# P1.net
KiCad netlist of a schematic drawn in EasyEDA Pro
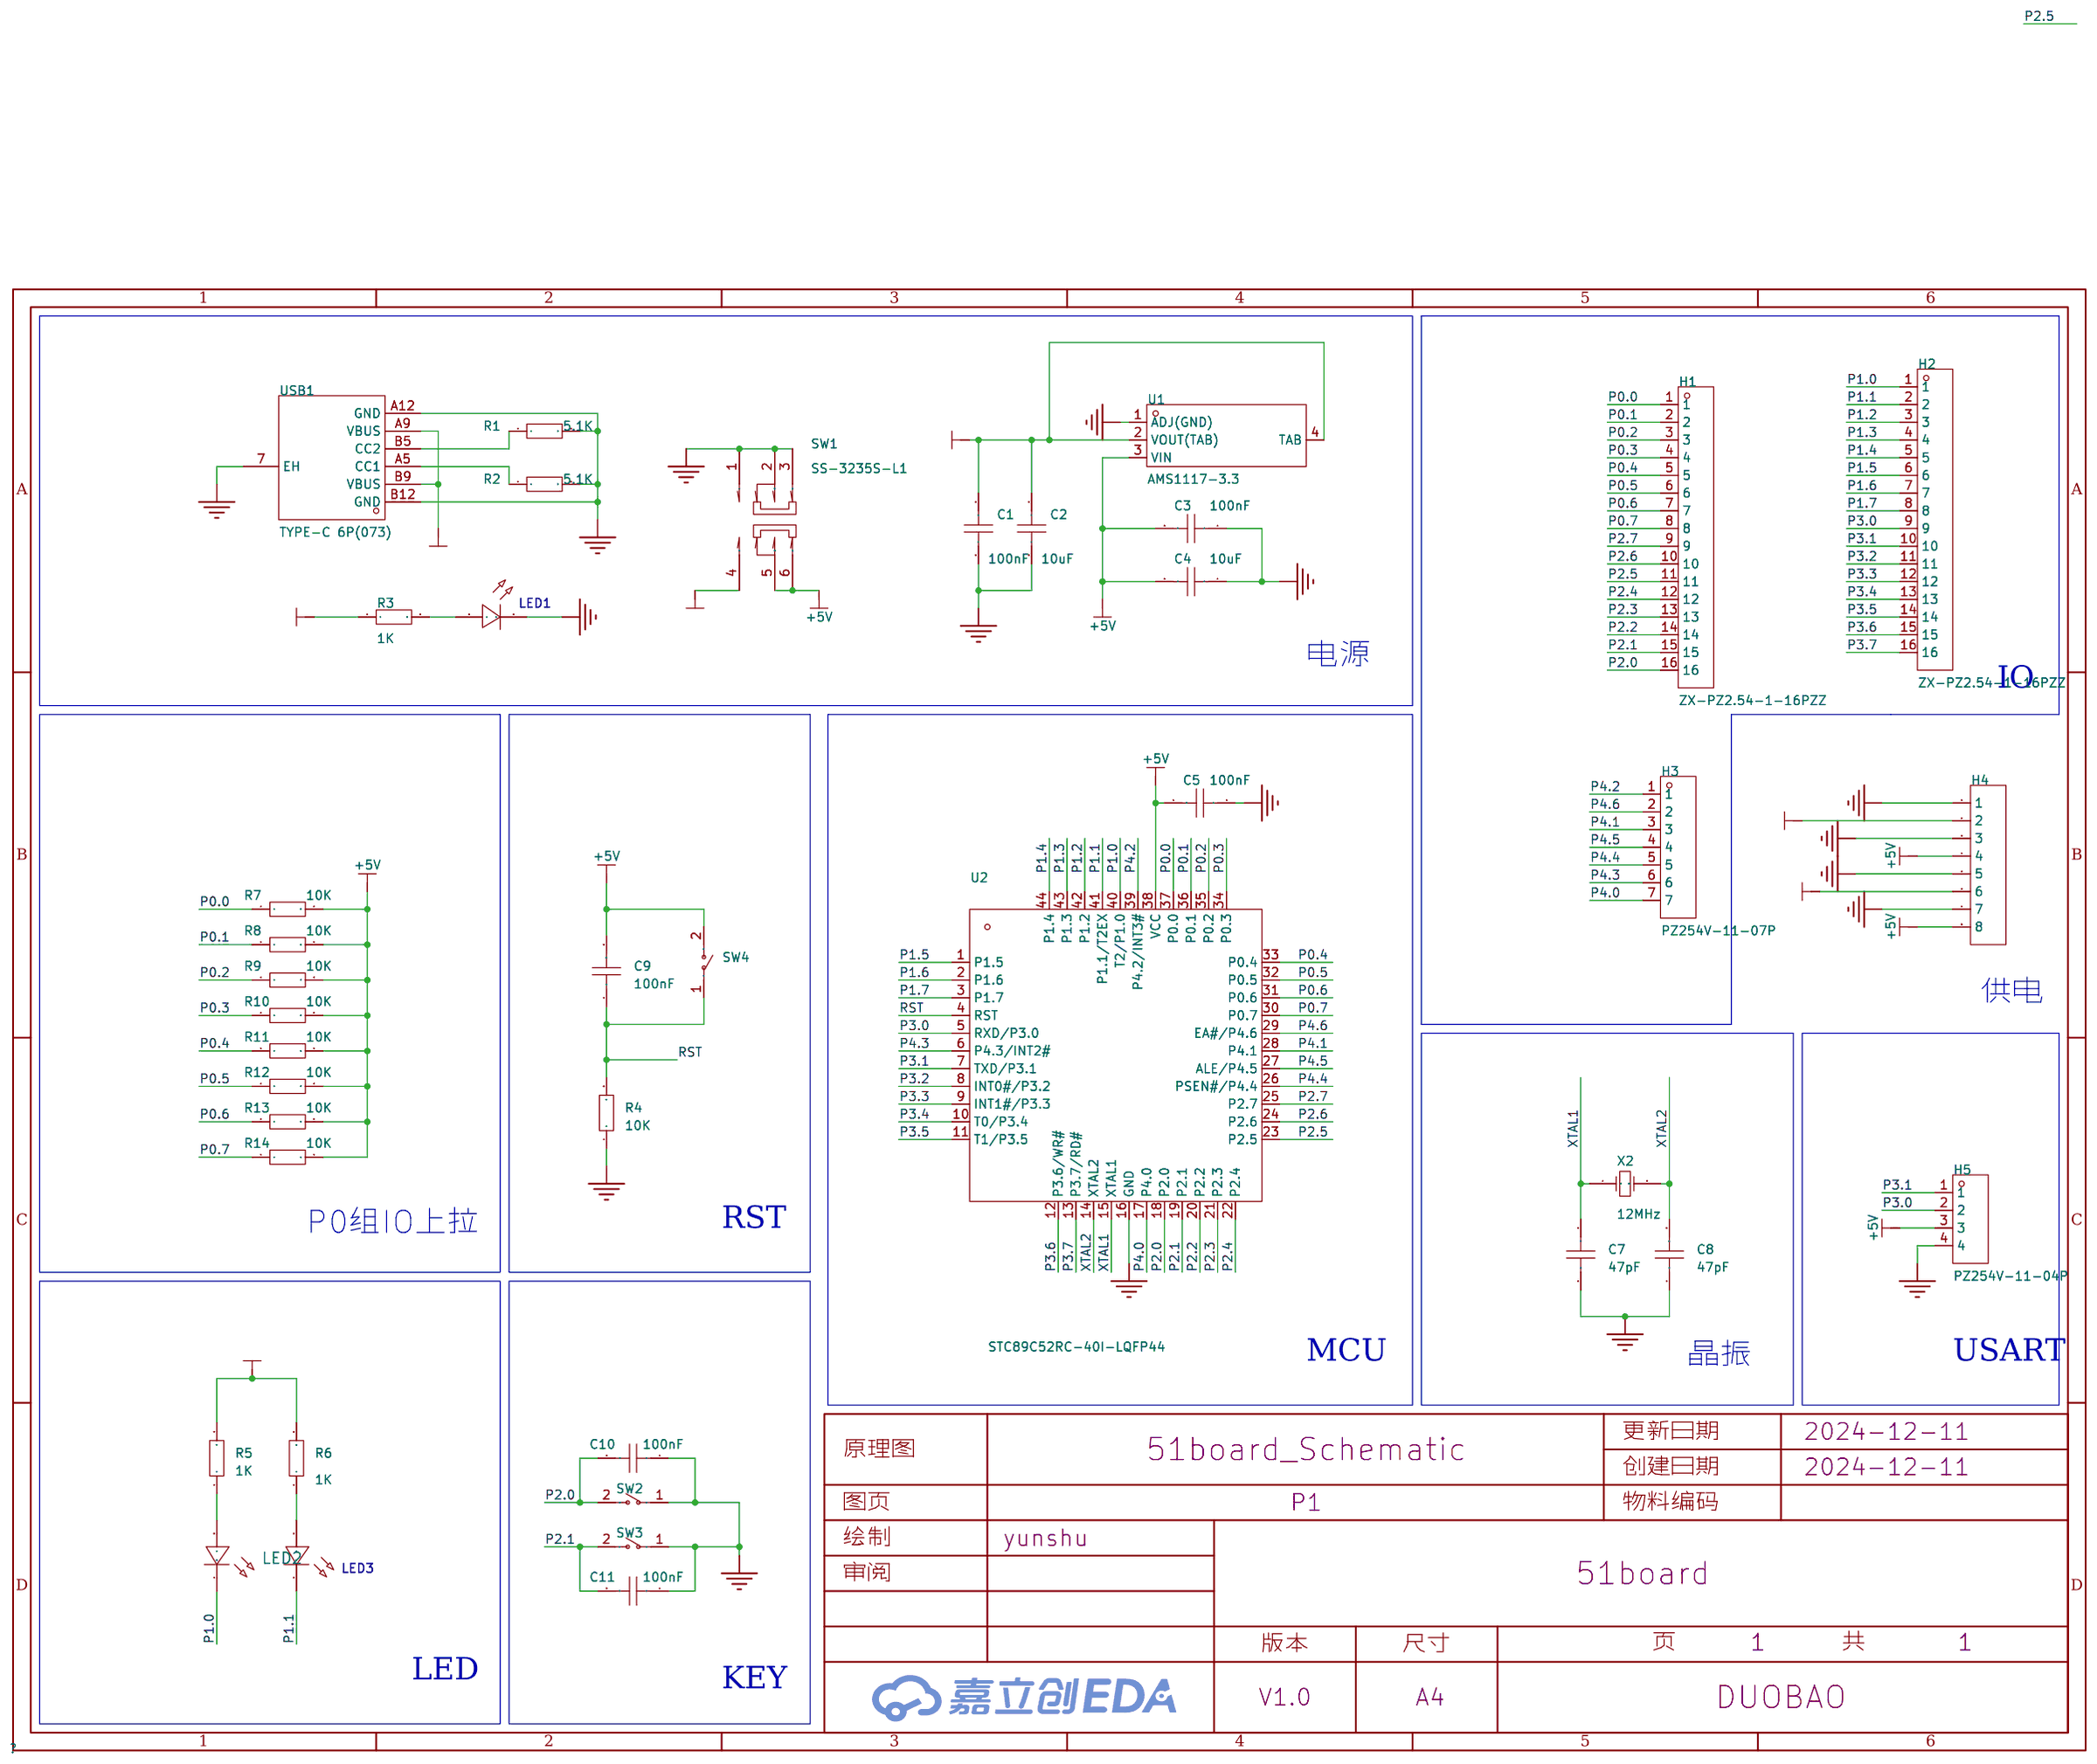
[diagram p0: schematic sheet]

(export (version "E")
  (design (tool "Eeschema 10.0.6"))
  (components
    (comp (ref "C1")
      (value "100nF")
      (footprint "easyedapro:C0805")
      (libsource (lib "easyedapro") (part "CapAcitance"))
    )
    (comp (ref "C2")
      (value "10uF")
      (footprint "easyedapro:C0805")
      (libsource (lib "easyedapro") (part "CapAcitance"))
    )
    (comp (ref "C3")
      (value "100nF")
      (footprint "easyedapro:C0805")
      (libsource (lib "easyedapro") (part "CapAcitance"))
    )
    (comp (ref "C4")
      (value "10uF")
      (footprint "easyedapro:C0805")
      (libsource (lib "easyedapro") (part "CapAcitance"))
    )
    (comp (ref "C5")
      (value "100nF")
      (footprint "easyedapro:C0805")
      (libsource (lib "easyedapro") (part "CapAcitance"))
    )
    (comp (ref "C7")
      (value "47pF")
      (footprint "easyedapro:C0805")
      (libsource (lib "easyedapro") (part "CapAcitance"))
    )
    (comp (ref "C8")
      (value "47pF")
      (footprint "easyedapro:C0805")
      (libsource (lib "easyedapro") (part "CapAcitance"))
    )
    (comp (ref "C9")
      (value "100nF")
      (footprint "easyedapro:C0805")
      (libsource (lib "easyedapro") (part "CapAcitance"))
    )
    (comp (ref "C10")
      (value "100nF")
      (footprint "easyedapro:C0805")
      (libsource (lib "easyedapro") (part "CapAcitance"))
    )
    (comp (ref "C11")
      (value "100nF")
      (footprint "easyedapro:C0805")
      (libsource (lib "easyedapro") (part "CapAcitance"))
    )
    (comp (ref "H1")
      (value "ZX-PZ2.54-1-16PZZ")
      (fields (field (name "Manufacturer") "Megastar(兆星)"))
      (libsource (lib "easyedapro") (part "HDR_2.54-1x16P"))
    )
    (comp (ref "H2")
      (value "ZX-PZ2.54-1-16PZZ")
      (fields (field (name "Manufacturer") "Megastar(兆星)"))
      (libsource (lib "easyedapro") (part "HDR_2.54-1x16P"))
    )
    (comp (ref "H3")
      (value "PZ254V-11-07P")
      (footprint "easyedapro:HDR-TH_7P-P2.54-V-M")
      (fields (field (name "Manufacturer") "XFCN(兴飞)"))
      (libsource (lib "easyedapro") (part "PZ254V-11-07P"))
    )
    (comp (ref "H4")
      (value "~")
      (footprint "easyedapro:HDR-TH_8P-P2.54-V-F-1")
      (libsource (lib "easyedapro") (part "Header-Female-2.54_1x8"))
    )
    (comp (ref "H5")
      (value "PZ254V-11-04P")
      (fields (field (name "Manufacturer") "XFCN(兴飞)"))
      (libsource (lib "easyedapro") (part "PZ254V-11-04P"))
    )
    (comp (ref "LED1")
      (value "~")
      (footprint "easyedapro:LED_0805")
      (libsource (lib "easyedapro") (part "LED_G"))
    )
    (comp (ref "LED2")
      (value "~")
      (footprint "easyedapro:LED_0805")
      (libsource (lib "easyedapro") (part "LED_R"))
    )
    (comp (ref "LED3")
      (value "~")
      (footprint "easyedapro:LED_0805")
      (libsource (lib "easyedapro") (part "LED_B"))
    )
    (comp (ref "R1") (value "5.1K") (footprint "easyedapro:R0805") (libsource (lib "easyedapro") (part "电阻")))
    (comp (ref "R2") (value "5.1K") (footprint "easyedapro:R0805") (libsource (lib "easyedapro") (part "电阻")))
    (comp (ref "R3") (value "1K") (footprint "easyedapro:R0805") (libsource (lib "easyedapro") (part "电阻")))
    (comp (ref "R4") (value "10K") (footprint "easyedapro:R0805") (libsource (lib "easyedapro") (part "电阻")))
    (comp (ref "R5") (value "1K") (footprint "easyedapro:R0805") (libsource (lib "easyedapro") (part "电阻")))
    (comp (ref "R6") (value "1K") (footprint "easyedapro:R0805") (libsource (lib "easyedapro") (part "电阻")))
    (comp (ref "R7") (value "10K") (footprint "easyedapro:R0805") (libsource (lib "easyedapro") (part "电阻")))
    (comp (ref "R8") (value "10K") (footprint "easyedapro:R0805") (libsource (lib "easyedapro") (part "电阻")))
    (comp (ref "R9") (value "10K") (footprint "easyedapro:R0805") (libsource (lib "easyedapro") (part "电阻")))
    (comp (ref "R10") (value "10K") (footprint "easyedapro:R0805") (libsource (lib "easyedapro") (part "电阻")))
    (comp (ref "R11") (value "10K") (footprint "easyedapro:R0805") (libsource (lib "easyedapro") (part "电阻")))
    (comp (ref "R12") (value "10K") (footprint "easyedapro:R0805") (libsource (lib "easyedapro") (part "电阻")))
    (comp (ref "R13") (value "10K") (footprint "easyedapro:R0805") (libsource (lib "easyedapro") (part "电阻")))
    (comp (ref "R14") (value "10K") (footprint "easyedapro:R0805") (libsource (lib "easyedapro") (part "电阻")))
    (comp (ref "SW1")
      (value "SS-3235S-L1")
      (footprint "easyedapro:SW-SMD_SS-3235S-LX")
      (description "电路结构:双刀双掷;安装方式:卧贴;开关颜色:黑色;额定电流(DC):50mA;额定电压(DC):12V;额定电流(AC):50mA;额定电压(AC):12V;机械寿命:1万次;")
      (fields (field (name "Manufacturer") "XKB Connectivity(中国星坤)"))
      (libsource (lib "easyedapro") (part "SS-3235S-L1"))
    )
    (comp (ref "SW2")
      (value "轻触按键 3x6x2.5mm")
      (footprint "easyedapro:SW-SMD_L6.1-W3.7-LS8.0")
      (description "开关长度:6.05mm;开关宽度:3.65mm;开关高度:2.5mm;机械寿命:-;")
      (fields (field (name "Manufacturer") "BBJ"))
      (libsource (lib "easyedapro") (part "轻触按键 3X6X2.5MM"))
    )
    (comp (ref "SW3")
      (value "轻触按键 3x6x2.5mm")
      (footprint "easyedapro:SW-SMD_L6.1-W3.7-LS8.0")
      (description "开关长度:6.05mm;开关宽度:3.65mm;开关高度:2.5mm;机械寿命:-;")
      (fields (field (name "Manufacturer") "BBJ"))
      (libsource (lib "easyedapro") (part "轻触按键 3X6X2.5MM"))
    )
    (comp (ref "SW4")
      (value "轻触按键 3x6x2.5mm")
      (footprint "easyedapro:SW-SMD_L6.1-W3.7-LS8.0")
      (description "开关长度:6.05mm;开关宽度:3.65mm;开关高度:2.5mm;机械寿命:-;")
      (fields (field (name "Manufacturer") "BBJ"))
      (libsource (lib "easyedapro") (part "轻触按键 3X6X2.5MM"))
    )
    (comp (ref "U1")
      (value "AMS1117-3.3")
      (footprint "easyedapro:SOT-223-4_L6.5-W3.5-P2.30-LS7.0-BR")
      (description "输出类型:固定;最大输入电压:18V;输出电压:3.3V;输出电流:1A;电源纹波抑制比(PSRR):60dB@(120Hz);输出极性:正极;")
      (fields (field (name "Manufacturer") "UMW(友台半导体)"))
      (libsource (lib "easyedapro") (part "AMS1117-3.3_C347222"))
    )
    (comp (ref "U2")
      (value "STC89C52RC-40I-LQFP44")
      (footprint "easyedapro:LQFP-44_L10.0-W10.0-P0.80-LS12.0-BL")
      (description "CPU内核:51系列;程序存储容量:8KB;RAM总容量:512Byte;GPIO端口数量:39;工作电压范围:3.3V~5.5V;CPU最大主频:-;程序存储器类型:FLASH;")
      (fields (field (name "Manufacturer") "STC(宏晶)"))
      (libsource (lib "easyedapro") (part "STC89C52RC-40I_C8707"))
    )
    (comp (ref "USB1")
      (value "TYPE-C 6P(073)")
      (footprint "easyedapro:TYPE-C-SMD_TYPE-C-6P_5")
      (description "连接器类型:Type-C;标准:USB 3.1;公母:母;安装方式:卧贴;触点数量:6P;端口数量:1;额定电流 - 电源:3A;工作温度范围:-25°C~+85°C;")
      (fields (field (name "Manufacturer") "SHOU HAN(首韩)"))
      (libsource (lib "easyedapro") (part "TYPE-C 6P(073)"))
    )
    (comp (ref "X2")
      (value "12MHz")
      (footprint "easyedapro:OSC-TH_BD2.0-P0.50")
      (description "晶振类型:直插晶振;频率:12MHz;常温频差:±20ppm;外接负载电容:20pF;频率稳定度(全温):±30ppm;")
      (fields
        (field (name "Manufacturer Part") "TXD12M0002206LDBEO00S")
        (field (name "Manufacturer") "YJX(雅晶鑫)")
      )
      (libsource (lib "easyedapro") (part "TXD12M0002206LDBEO00S"))
    )
  )
  (nets
    (net (code "1") (name "+5V") (class "Default")
      (node (ref "C3") (pin "2") (pinfunction "2_2") (pintype "input"))
      (node (ref "C4") (pin "2") (pinfunction "2_2") (pintype "input"))
      (node (ref "C5") (pin "1") (pinfunction "1_1") (pintype "input"))
      (node (ref "C9") (pin "2") (pinfunction "2_2") (pintype "input"))
      (node (ref "H4") (pin "4") (pinfunction "4_4") (pintype "input"))
      (node (ref "H4") (pin "8") (pinfunction "8_8") (pintype "input"))
      (node (ref "H5") (pin "3") (pinfunction "3_3") (pintype "unspecified"))
      (node (ref "R10") (pin "2") (pinfunction "2_2") (pintype "input"))
      (node (ref "R11") (pin "2") (pinfunction "2_2") (pintype "input"))
      (node (ref "R12") (pin "2") (pinfunction "2_2") (pintype "input"))
      (node (ref "R13") (pin "2") (pinfunction "2_2") (pintype "input"))
      (node (ref "R14") (pin "2") (pinfunction "2_2") (pintype "input"))
      (node (ref "R7") (pin "2") (pinfunction "2_2") (pintype "input"))
      (node (ref "R8") (pin "2") (pinfunction "2_2") (pintype "input"))
      (node (ref "R9") (pin "2") (pinfunction "2_2") (pintype "input"))
      (node (ref "SW1") (pin "5") (pinfunction "5_5") (pintype "unspecified"))
      (node (ref "SW1") (pin "6") (pinfunction "6_6") (pintype "unspecified"))
      (node (ref "SW4") (pin "2") (pinfunction "2_2") (pintype "unspecified"))
      (node (ref "U1") (pin "3") (pinfunction "VIN_3") (pintype "unspecified"))
      (node (ref "U2") (pin "38") (pinfunction "VCC_38") (pintype "unspecified"))
    )
    (net (code "2") (name "/P0.0") (class "Default")
      (node (ref "H1") (pin "1") (pinfunction "1_1") (pintype "input"))
      (node (ref "R7") (pin "1") (pinfunction "1_1") (pintype "input"))
      (node (ref "U2") (pin "37") (pinfunction "P0.0_37") (pintype "unspecified"))
    )
    (net (code "3") (name "/P0.1") (class "Default")
      (node (ref "H1") (pin "2") (pinfunction "2_2") (pintype "input"))
      (node (ref "R8") (pin "1") (pinfunction "1_1") (pintype "input"))
      (node (ref "U2") (pin "36") (pinfunction "P0.1_36") (pintype "unspecified"))
    )
    (net (code "4") (name "/P0.2") (class "Default")
      (node (ref "H1") (pin "3") (pinfunction "3_3") (pintype "input"))
      (node (ref "R9") (pin "1") (pinfunction "1_1") (pintype "input"))
      (node (ref "U2") (pin "35") (pinfunction "P0.2_35") (pintype "unspecified"))
    )
    (net (code "5") (name "/P0.3") (class "Default")
      (node (ref "H1") (pin "4") (pinfunction "4_4") (pintype "input"))
      (node (ref "R10") (pin "1") (pinfunction "1_1") (pintype "input"))
      (node (ref "U2") (pin "34") (pinfunction "P0.3_34") (pintype "unspecified"))
    )
    (net (code "6") (name "/P0.4") (class "Default")
      (node (ref "H1") (pin "5") (pinfunction "5_5") (pintype "input"))
      (node (ref "R11") (pin "1") (pinfunction "1_1") (pintype "input"))
      (node (ref "U2") (pin "33") (pinfunction "P0.4_33") (pintype "unspecified"))
    )
    (net (code "7") (name "/P0.5") (class "Default")
      (node (ref "H1") (pin "6") (pinfunction "6_6") (pintype "input"))
      (node (ref "R12") (pin "1") (pinfunction "1_1") (pintype "input"))
      (node (ref "U2") (pin "32") (pinfunction "P0.5_32") (pintype "unspecified"))
    )
    (net (code "8") (name "/P0.6") (class "Default")
      (node (ref "H1") (pin "7") (pinfunction "7_7") (pintype "input"))
      (node (ref "R13") (pin "1") (pinfunction "1_1") (pintype "input"))
      (node (ref "U2") (pin "31") (pinfunction "P0.6_31") (pintype "unspecified"))
    )
    (net (code "9") (name "/P0.7") (class "Default")
      (node (ref "H1") (pin "8") (pinfunction "8_8") (pintype "input"))
      (node (ref "R14") (pin "1") (pinfunction "1_1") (pintype "input"))
      (node (ref "U2") (pin "30") (pinfunction "P0.7_30") (pintype "unspecified"))
    )
    (net (code "10") (name "/P1.0") (class "Default")
      (node (ref "H2") (pin "1") (pinfunction "1_1") (pintype "input"))
      (node (ref "LED2") (pin "1") (pinfunction "C_1") (pintype "input"))
      (node (ref "U2") (pin "40") (pinfunction "T2/P1.0_40") (pintype "unspecified"))
    )
    (net (code "11") (name "/P1.1") (class "Default")
      (node (ref "H2") (pin "2") (pinfunction "2_2") (pintype "input"))
      (node (ref "LED3") (pin "1") (pinfunction "C_1") (pintype "input"))
      (node (ref "U2") (pin "41") (pinfunction "P1.1/T2EX_41") (pintype "unspecified"))
    )
    (net (code "12") (name "/P1.2") (class "Default")
      (node (ref "H2") (pin "3") (pinfunction "3_3") (pintype "input"))
      (node (ref "U2") (pin "42") (pinfunction "P1.2_42") (pintype "unspecified"))
    )
    (net (code "13") (name "/P1.3") (class "Default")
      (node (ref "H2") (pin "4") (pinfunction "4_4") (pintype "input"))
      (node (ref "U2") (pin "43") (pinfunction "P1.3_43") (pintype "unspecified"))
    )
    (net (code "14") (name "/P1.4") (class "Default")
      (node (ref "H2") (pin "5") (pinfunction "5_5") (pintype "input"))
      (node (ref "U2") (pin "44") (pinfunction "P1.4_44") (pintype "unspecified"))
    )
    (net (code "15") (name "/P1.5") (class "Default")
      (node (ref "H2") (pin "6") (pinfunction "6_6") (pintype "input"))
      (node (ref "U2") (pin "1") (pinfunction "P1.5_1") (pintype "unspecified"))
    )
    (net (code "16") (name "/P1.6") (class "Default")
      (node (ref "H2") (pin "7") (pinfunction "7_7") (pintype "input"))
      (node (ref "U2") (pin "2") (pinfunction "P1.6_2") (pintype "unspecified"))
    )
    (net (code "17") (name "/P1.7") (class "Default")
      (node (ref "H2") (pin "8") (pinfunction "8_8") (pintype "input"))
      (node (ref "U2") (pin "3") (pinfunction "P1.7_3") (pintype "unspecified"))
    )
    (net (code "18") (name "/P2.0") (class "Default")
      (node (ref "C10") (pin "2") (pinfunction "2_2") (pintype "input"))
      (node (ref "H1") (pin "16") (pinfunction "16_16") (pintype "input"))
      (node (ref "SW2") (pin "2") (pinfunction "2_2") (pintype "unspecified"))
      (node (ref "U2") (pin "18") (pinfunction "P2.0_18") (pintype "unspecified"))
    )
    (net (code "19") (name "/P2.1") (class "Default")
      (node (ref "C11") (pin "2") (pinfunction "2_2") (pintype "input"))
      (node (ref "H1") (pin "15") (pinfunction "15_15") (pintype "input"))
      (node (ref "SW3") (pin "2") (pinfunction "2_2") (pintype "unspecified"))
      (node (ref "U2") (pin "19") (pinfunction "P2.1_19") (pintype "unspecified"))
    )
    (net (code "20") (name "/P2.2") (class "Default")
      (node (ref "H1") (pin "14") (pinfunction "14_14") (pintype "input"))
      (node (ref "U2") (pin "20") (pinfunction "P2.2_20") (pintype "unspecified"))
    )
    (net (code "21") (name "/P2.3") (class "Default")
      (node (ref "H1") (pin "13") (pinfunction "13_13") (pintype "input"))
      (node (ref "U2") (pin "21") (pinfunction "P2.3_21") (pintype "unspecified"))
    )
    (net (code "22") (name "/P2.4") (class "Default")
      (node (ref "H1") (pin "12") (pinfunction "12_12") (pintype "input"))
      (node (ref "U2") (pin "22") (pinfunction "P2.4_22") (pintype "unspecified"))
    )
    (net (code "23") (name "/P2.5") (class "Default")
      (node (ref "H1") (pin "11") (pinfunction "11_11") (pintype "input"))
      (node (ref "U2") (pin "23") (pinfunction "P2.5_23") (pintype "unspecified"))
    )
    (net (code "24") (name "/P2.6") (class "Default")
      (node (ref "H1") (pin "10") (pinfunction "10_10") (pintype "input"))
      (node (ref "U2") (pin "24") (pinfunction "P2.6_24") (pintype "unspecified"))
    )
    (net (code "25") (name "/P2.7") (class "Default")
      (node (ref "H1") (pin "9") (pinfunction "9_9") (pintype "input"))
      (node (ref "U2") (pin "25") (pinfunction "P2.7_25") (pintype "unspecified"))
    )
    (net (code "26") (name "/P3.0") (class "Default")
      (node (ref "H2") (pin "9") (pinfunction "9_9") (pintype "input"))
      (node (ref "H5") (pin "2") (pinfunction "2_2") (pintype "unspecified"))
      (node (ref "U2") (pin "5") (pinfunction "RXD/P3.0_5") (pintype "unspecified"))
    )
    (net (code "27") (name "/P3.1") (class "Default")
      (node (ref "H2") (pin "10") (pinfunction "10_10") (pintype "input"))
      (node (ref "H5") (pin "1") (pinfunction "1_1") (pintype "unspecified"))
      (node (ref "U2") (pin "7") (pinfunction "TXD/P3.1_7") (pintype "unspecified"))
    )
    (net (code "28") (name "/P3.2") (class "Default")
      (node (ref "H2") (pin "11") (pinfunction "11_11") (pintype "input"))
      (node (ref "U2") (pin "8") (pinfunction "INT0#/P3.2_8") (pintype "unspecified"))
    )
    (net (code "29") (name "/P3.3") (class "Default")
      (node (ref "H2") (pin "12") (pinfunction "12_12") (pintype "input"))
      (node (ref "U2") (pin "9") (pinfunction "INT1#/P3.3_9") (pintype "unspecified"))
    )
    (net (code "30") (name "/P3.4") (class "Default")
      (node (ref "H2") (pin "13") (pinfunction "13_13") (pintype "input"))
      (node (ref "U2") (pin "10") (pinfunction "T0/P3.4_10") (pintype "unspecified"))
    )
    (net (code "31") (name "/P3.5") (class "Default")
      (node (ref "H2") (pin "14") (pinfunction "14_14") (pintype "input"))
      (node (ref "U2") (pin "11") (pinfunction "T1/P3.5_11") (pintype "unspecified"))
    )
    (net (code "32") (name "/P3.6") (class "Default")
      (node (ref "H2") (pin "15") (pinfunction "15_15") (pintype "input"))
      (node (ref "U2") (pin "12") (pinfunction "P3.6/WR#_12") (pintype "unspecified"))
    )
    (net (code "33") (name "/P3.7") (class "Default")
      (node (ref "H2") (pin "16") (pinfunction "16_16") (pintype "input"))
      (node (ref "U2") (pin "13") (pinfunction "P3.7/RD#_13") (pintype "unspecified"))
    )
    (net (code "34") (name "/P4.0") (class "Default")
      (node (ref "H3") (pin "7") (pinfunction "7_7") (pintype "unspecified"))
      (node (ref "U2") (pin "17") (pinfunction "P4.0_17") (pintype "unspecified"))
    )
    (net (code "35") (name "/P4.1") (class "Default")
      (node (ref "H3") (pin "3") (pinfunction "3_3") (pintype "unspecified"))
      (node (ref "U2") (pin "28") (pinfunction "P4.1_28") (pintype "unspecified"))
    )
    (net (code "36") (name "/P4.2") (class "Default")
      (node (ref "H3") (pin "1") (pinfunction "1_1") (pintype "unspecified"))
      (node (ref "U2") (pin "39") (pinfunction "P4.2/INT3#_39") (pintype "unspecified"))
    )
    (net (code "37") (name "/P4.3") (class "Default")
      (node (ref "H3") (pin "6") (pinfunction "6_6") (pintype "unspecified"))
      (node (ref "U2") (pin "6") (pinfunction "P4.3/INT2#_6") (pintype "unspecified"))
    )
    (net (code "38") (name "/P4.4") (class "Default")
      (node (ref "H3") (pin "5") (pinfunction "5_5") (pintype "unspecified"))
      (node (ref "U2") (pin "26") (pinfunction "PSEN#/P4.4_26") (pintype "unspecified"))
    )
    (net (code "39") (name "/P4.5") (class "Default")
      (node (ref "H3") (pin "4") (pinfunction "4_4") (pintype "unspecified"))
      (node (ref "U2") (pin "27") (pinfunction "ALE/P4.5_27") (pintype "unspecified"))
    )
    (net (code "40") (name "/P4.6") (class "Default")
      (node (ref "H3") (pin "2") (pinfunction "2_2") (pintype "unspecified"))
      (node (ref "U2") (pin "29") (pinfunction "EA#/P4.6_29") (pintype "unspecified"))
    )
    (net (code "41") (name "/RST") (class "Default")
      (node (ref "C9") (pin "1") (pinfunction "1_1") (pintype "input"))
      (node (ref "R4") (pin "2") (pinfunction "2_2") (pintype "input"))
      (node (ref "SW4") (pin "1") (pinfunction "1_1") (pintype "unspecified"))
      (node (ref "U2") (pin "4") (pinfunction "RST_4") (pintype "unspecified"))
    )
    (net (code "42") (name "/XTAL1") (class "Default")
      (node (ref "C7") (pin "2") (pinfunction "2_2") (pintype "input"))
      (node (ref "U2") (pin "15") (pinfunction "XTAL1_15") (pintype "unspecified"))
      (node (ref "X2") (pin "1") (pinfunction "OSC1_1") (pintype "unspecified"))
    )
    (net (code "43") (name "/XTAL2") (class "Default")
      (node (ref "C8") (pin "2") (pinfunction "2_2") (pintype "input"))
      (node (ref "U2") (pin "14") (pinfunction "XTAL2_14") (pintype "unspecified"))
      (node (ref "X2") (pin "2") (pinfunction "OSC2_2") (pintype "unspecified"))
    )
    (net (code "44") (name "GND") (class "Default")
      (node (ref "C1") (pin "2") (pinfunction "2_2") (pintype "input"))
      (node (ref "C10") (pin "1") (pinfunction "1_1") (pintype "input"))
      (node (ref "C11") (pin "1") (pinfunction "1_1") (pintype "input"))
      (node (ref "C2") (pin "2") (pinfunction "2_2") (pintype "input"))
      (node (ref "C3") (pin "1") (pinfunction "1_1") (pintype "input"))
      (node (ref "C4") (pin "1") (pinfunction "1_1") (pintype "input"))
      (node (ref "C5") (pin "2") (pinfunction "2_2") (pintype "input"))
      (node (ref "C7") (pin "1") (pinfunction "1_1") (pintype "input"))
      (node (ref "C8") (pin "1") (pinfunction "1_1") (pintype "input"))
      (node (ref "H4") (pin "1") (pinfunction "1_1") (pintype "input"))
      (node (ref "H4") (pin "3") (pinfunction "3_3") (pintype "input"))
      (node (ref "H4") (pin "5") (pinfunction "5_5") (pintype "input"))
      (node (ref "H4") (pin "7") (pinfunction "7_7") (pintype "input"))
      (node (ref "H5") (pin "4") (pinfunction "4_4") (pintype "unspecified"))
      (node (ref "LED1") (pin "1") (pinfunction "C_1") (pintype "input"))
      (node (ref "R1") (pin "2") (pinfunction "2_2") (pintype "input"))
      (node (ref "R2") (pin "2") (pinfunction "2_2") (pintype "input"))
      (node (ref "R4") (pin "1") (pinfunction "1_1") (pintype "input"))
      (node (ref "SW1") (pin "1") (pinfunction "1_1") (pintype "unspecified"))
      (node (ref "SW1") (pin "2") (pinfunction "2_2") (pintype "unspecified"))
      (node (ref "SW1") (pin "3") (pinfunction "3_3") (pintype "unspecified"))
      (node (ref "SW2") (pin "1") (pinfunction "1_1") (pintype "unspecified"))
      (node (ref "SW3") (pin "1") (pinfunction "1_1") (pintype "unspecified"))
      (node (ref "U1") (pin "1") (pinfunction "ADJ(GND)_1") (pintype "unspecified"))
      (node (ref "U2") (pin "16") (pinfunction "GND_16") (pintype "unspecified"))
      (node (ref "USB1") (pin "7") (pinfunction "EH_7") (pintype "unspecified"))
      (node (ref "USB1") (pin "A12") (pinfunction "GND_A12") (pintype "unspecified"))
      (node (ref "USB1") (pin "B12") (pinfunction "GND_B12") (pintype "unspecified"))
    )
    (net (code "45") (name "Net-(LED1-A)") (class "Default")
      (node (ref "LED1") (pin "2") (pinfunction "A_2") (pintype "input"))
      (node (ref "R3") (pin "2") (pinfunction "2_2") (pintype "input"))
    )
    (net (code "46") (name "Net-(LED2-A)") (class "Default")
      (node (ref "LED2") (pin "2") (pinfunction "A_2") (pintype "input"))
      (node (ref "R5") (pin "1") (pinfunction "1_1") (pintype "input"))
    )
    (net (code "47") (name "Net-(LED3-A)") (class "Default")
      (node (ref "LED3") (pin "2") (pinfunction "A_2") (pintype "input"))
      (node (ref "R6") (pin "1") (pinfunction "1_1") (pintype "input"))
    )
    (net (code "48") (name "Net-(USB1-CC1)") (class "Default")
      (node (ref "R2") (pin "1") (pinfunction "1_1") (pintype "input"))
      (node (ref "USB1") (pin "A5") (pinfunction "CC1_A5") (pintype "unspecified"))
    )
    (net (code "49") (name "Net-(USB1-CC2)") (class "Default")
      (node (ref "R1") (pin "1") (pinfunction "1_1") (pintype "input"))
      (node (ref "USB1") (pin "B5") (pinfunction "CC2_B5") (pintype "unspecified"))
    )
    (net (code "50") (name "VCC+3.3V") (class "Default")
      (node (ref "C1") (pin "1") (pinfunction "1_1") (pintype "input"))
      (node (ref "C2") (pin "1") (pinfunction "1_1") (pintype "input"))
      (node (ref "H4") (pin "2") (pinfunction "2_2") (pintype "input"))
      (node (ref "H4") (pin "6") (pinfunction "6_6") (pintype "input"))
      (node (ref "R3") (pin "1") (pinfunction "1_1") (pintype "input"))
      (node (ref "R5") (pin "2") (pinfunction "2_2") (pintype "input"))
      (node (ref "R6") (pin "2") (pinfunction "2_2") (pintype "input"))
      (node (ref "U1") (pin "2") (pinfunction "VOUT(TAB)_2") (pintype "unspecified"))
      (node (ref "U1") (pin "4") (pinfunction "TAB_4") (pintype "unspecified"))
    )
    (net (code "51") (name "VCC+5V") (class "Default")
      (node (ref "SW1") (pin "4") (pinfunction "4_4") (pintype "unspecified"))
      (node (ref "USB1") (pin "A9") (pinfunction "VBUS_A9") (pintype "unspecified"))
      (node (ref "USB1") (pin "B9") (pinfunction "VBUS_B9") (pintype "unspecified"))
    )
  )
)
